# 2225_VumetreFrequencemetre.net
KiCad netlist of a schematic drawn in Altium Designer
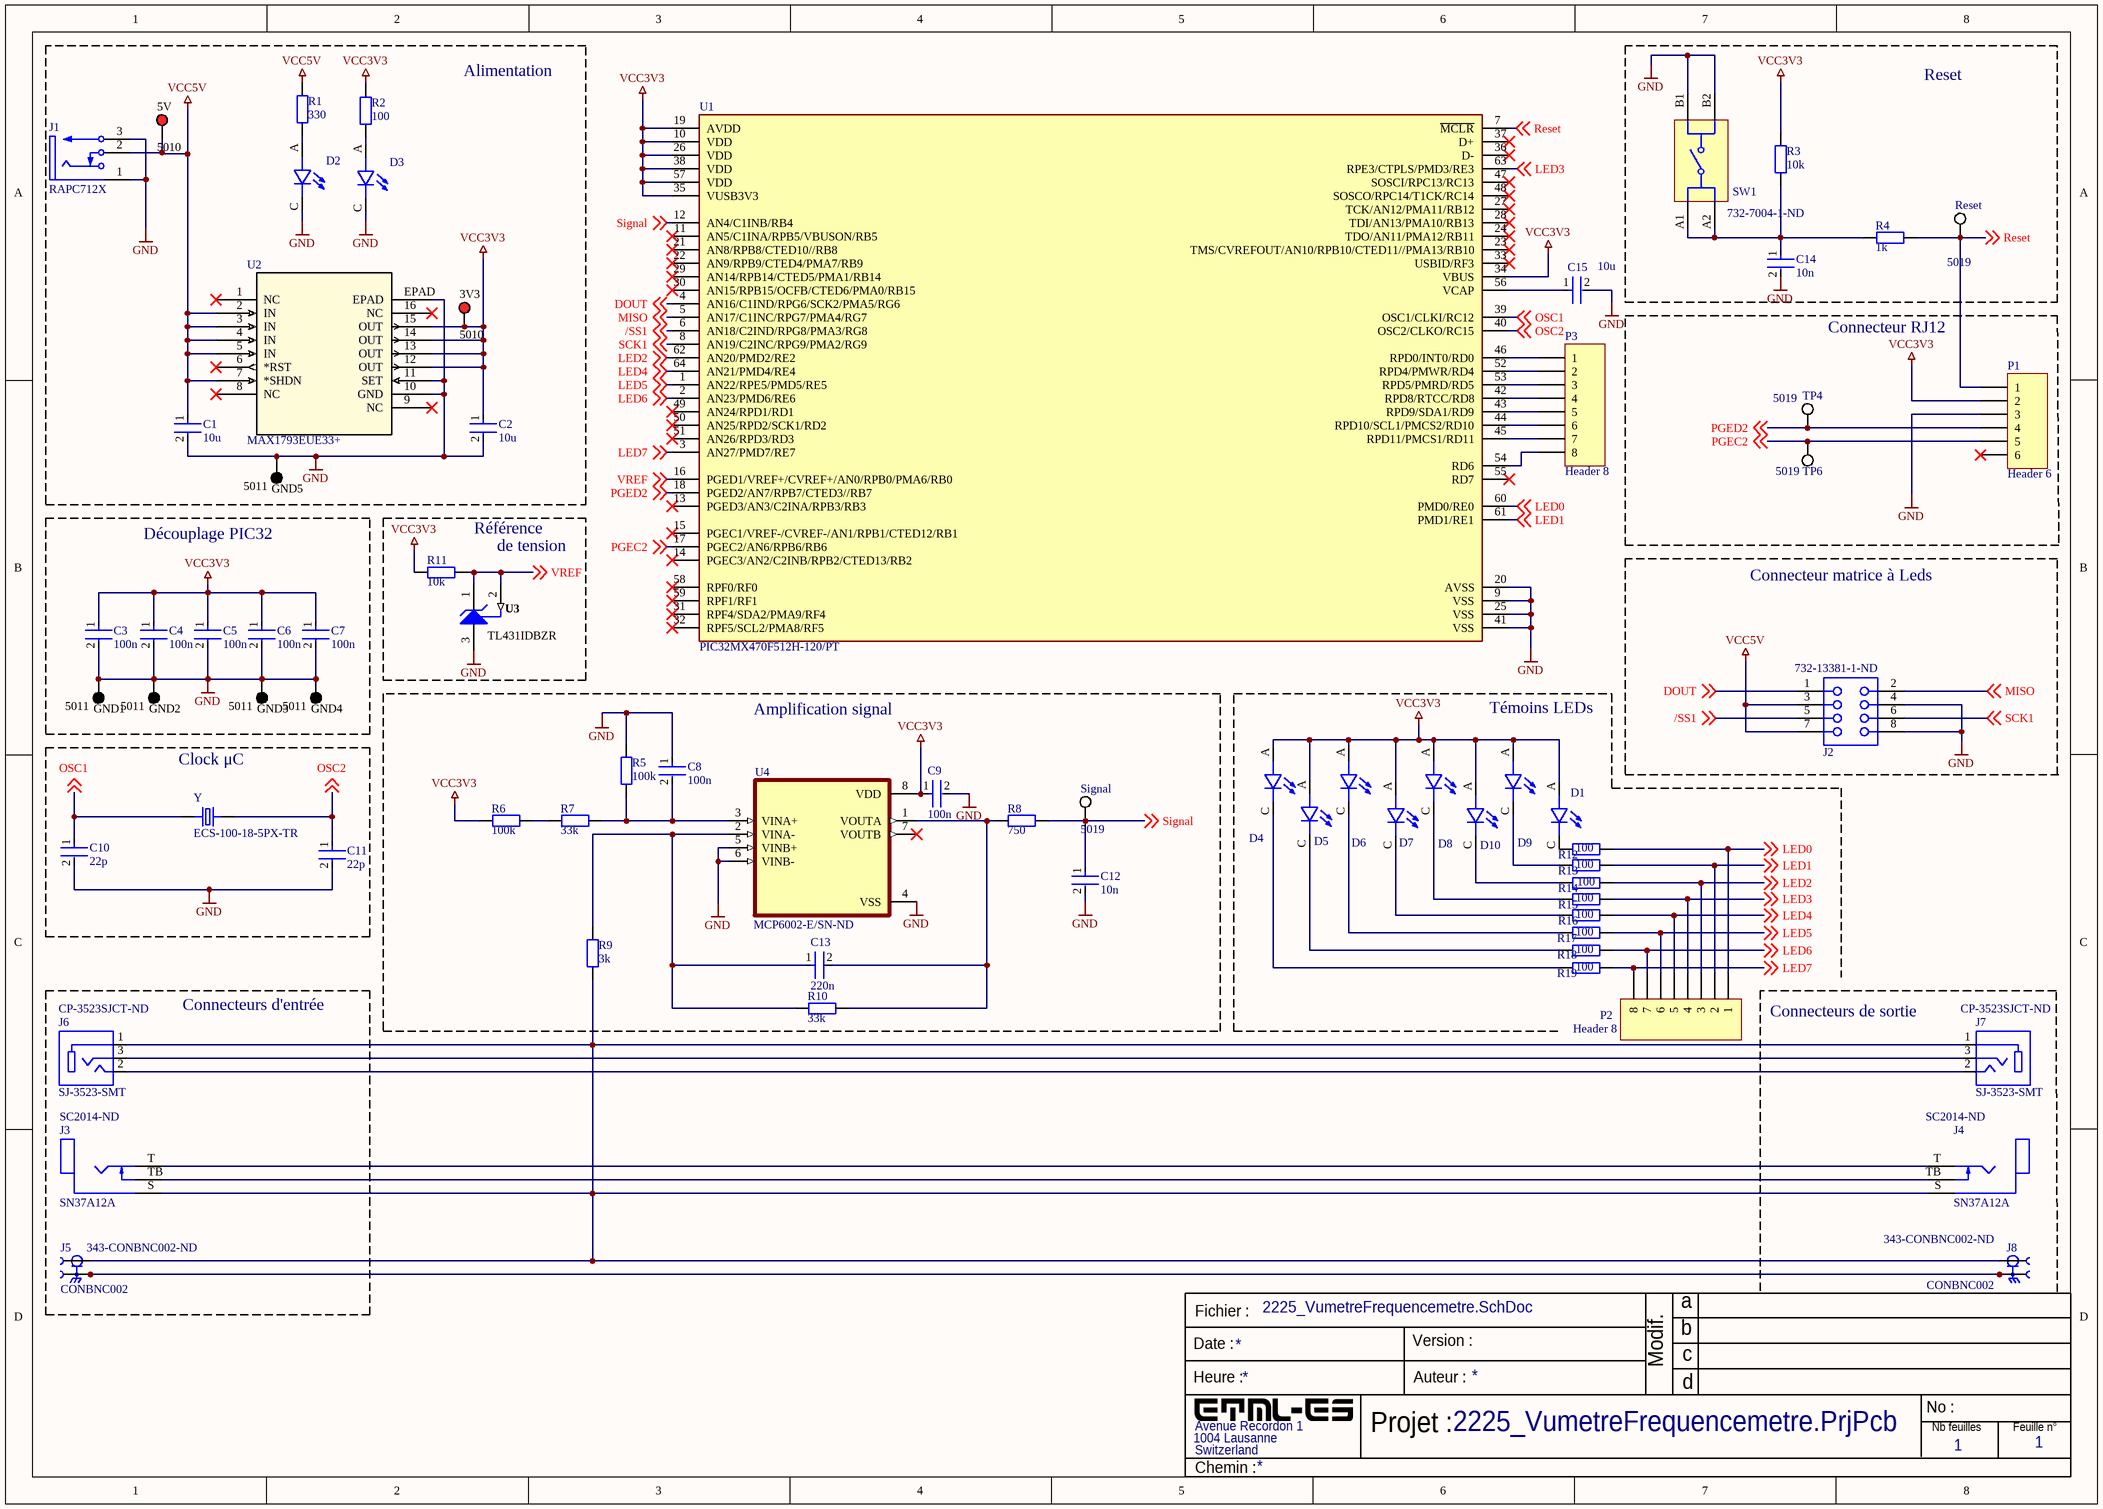
[diagram p0: 2225_VumetreFrequencemetre.SchDoc]

(export (version "E")
  (design (tool "Eeschema 10.0.6"))
  (components
    (comp (ref "3V3")
      (value "5010")
      (footprint "KSTN-5010_V")
      (description "Test Point, Red, Through Hole, RoHS, Bulk")
      (fields (field (name "MANUFACTURER") "Keystone"))
      (libsource (lib "Altium Content Vault") (part "TESTPOINT_RED"))
    )
    (comp (ref "5V")
      (value "5010")
      (footprint "KSTN-5010_V")
      (description "Test Point, Red, Through Hole, RoHS, Bulk")
      (fields (field (name "MANUFACTURER") "Keystone"))
      (libsource (lib "Altium Content Vault") (part "TESTPOINT_RED"))
    )
    (comp (ref "C1")
      (value "10u")
      (footprint "FP-GRM21B-0_15-IPC_C")
      (description "Chip Multilayer Ceramic Capacitors for General Purpose, 0805, 10uF, X5R, 15%, 10%, 25V")
      (fields (field (name "VOLTAGE") "25V") (field (name "TOLERANCE") "10%"))
      (libsource (lib "Altium Content Vault") (part "b4654b650e69147ec39a6b967a45e02"))
    )
    (comp (ref "C2")
      (value "10u")
      (footprint "FP-GRM21B-0_15-IPC_C")
      (description "Chip Multilayer Ceramic Capacitors for General Purpose, 0805, 10uF, X5R, 15%, 10%, 25V")
      (fields (field (name "VOLTAGE") "25V") (field (name "TOLERANCE") "10%"))
      (libsource (lib "Altium Content Vault") (part "b4654b650e69147ec39a6b967a45e02"))
    )
    (comp (ref "C3")
      (value "100n")
      (footprint "FP-GRM21B-0_15-IPC_C")
      (description "Chip Multilayer Ceramic Capacitors for General Purpose, 0805, 10uF, X5R, 15%, 10%, 25V")
      (fields (field (name "VOLTAGE") "25V") (field (name "TOLERANCE") "10%"))
      (libsource (lib "Altium Content Vault") (part "b4654b650e69147ec39a6b967a45e02"))
    )
    (comp (ref "C4")
      (value "100n")
      (footprint "FP-GRM21B-0_15-IPC_C")
      (description "Chip Multilayer Ceramic Capacitors for General Purpose, 0805, 10uF, X5R, 15%, 10%, 25V")
      (fields (field (name "VOLTAGE") "25V") (field (name "TOLERANCE") "10%"))
      (libsource (lib "Altium Content Vault") (part "b4654b650e69147ec39a6b967a45e02"))
    )
    (comp (ref "C5")
      (value "100n")
      (footprint "FP-GRM21B-0_15-IPC_C")
      (description "Chip Multilayer Ceramic Capacitors for General Purpose, 0805, 10uF, X5R, 15%, 10%, 25V")
      (fields (field (name "VOLTAGE") "25V") (field (name "TOLERANCE") "10%"))
      (libsource (lib "Altium Content Vault") (part "b4654b650e69147ec39a6b967a45e02"))
    )
    (comp (ref "C6")
      (value "100n")
      (footprint "FP-GRM21B-0_15-IPC_C")
      (description "Chip Multilayer Ceramic Capacitors for General Purpose, 0805, 10uF, X5R, 15%, 10%, 25V")
      (fields (field (name "VOLTAGE") "25V") (field (name "TOLERANCE") "10%"))
      (libsource (lib "Altium Content Vault") (part "b4654b650e69147ec39a6b967a45e02"))
    )
    (comp (ref "C7")
      (value "100n")
      (footprint "FP-GRM21B-0_15-IPC_C")
      (description "Chip Multilayer Ceramic Capacitors for General Purpose, 0805, 10uF, X5R, 15%, 10%, 25V")
      (fields (field (name "VOLTAGE") "25V") (field (name "TOLERANCE") "10%"))
      (libsource (lib "Altium Content Vault") (part "b4654b650e69147ec39a6b967a45e02"))
    )
    (comp (ref "C8")
      (value "100n")
      (footprint "FP-GRM21B-0_15-IPC_C")
      (description "Chip Multilayer Ceramic Capacitors for General Purpose, 0805, 10uF, X5R, 15%, 10%, 25V")
      (fields (field (name "VOLTAGE") "25V") (field (name "TOLERANCE") "10%"))
      (libsource (lib "Altium Content Vault") (part "b4654b650e69147ec39a6b967a45e02"))
    )
    (comp (ref "C9")
      (value "100n")
      (footprint "FP-GRM21B-0_15-IPC_C")
      (description "Chip Multilayer Ceramic Capacitors for General Purpose, 0805, 10uF, X5R, 15%, 10%, 25V")
      (fields (field (name "VOLTAGE") "25V") (field (name "TOLERANCE") "10%"))
      (libsource (lib "Altium Content Vault") (part "b4654b650e69147ec39a6b967a45e02"))
    )
    (comp (ref "C10")
      (value "22p")
      (footprint "FP-GRM21B-0_15-IPC_C")
      (description "Chip Multilayer Ceramic Capacitors for General Purpose, 0805, 10uF, X5R, 15%, 10%, 25V")
      (fields (field (name "VOLTAGE") "25V") (field (name "TOLERANCE") "10%"))
      (libsource (lib "Altium Content Vault") (part "b4654b650e69147ec39a6b967a45e02"))
    )
    (comp (ref "C11")
      (value "22p")
      (footprint "FP-GRM21B-0_15-IPC_C")
      (description "Chip Multilayer Ceramic Capacitors for General Purpose, 0805, 10uF, X5R, 15%, 10%, 25V")
      (fields (field (name "VOLTAGE") "25V") (field (name "TOLERANCE") "10%"))
      (libsource (lib "Altium Content Vault") (part "b4654b650e69147ec39a6b967a45e02"))
    )
    (comp (ref "C12")
      (value "10n")
      (footprint "FP-GRM21B-0_15-IPC_C")
      (description "Chip Multilayer Ceramic Capacitors for General Purpose, 0805, 10uF, X5R, 15%, 10%, 25V")
      (fields (field (name "VOLTAGE") "25V") (field (name "TOLERANCE") "10%"))
      (libsource (lib "Altium Content Vault") (part "b4654b650e69147ec39a6b967a45e02"))
    )
    (comp (ref "C13")
      (value "220n")
      (footprint "FP-GRM21B-0_15-IPC_C")
      (description "Chip Multilayer Ceramic Capacitors for General Purpose, 0805, 10uF, X5R, 15%, 10%, 25V")
      (fields (field (name "VOLTAGE") "25V") (field (name "TOLERANCE") "10%"))
      (libsource (lib "Altium Content Vault") (part "b4654b650e69147ec39a6b967a45e02"))
    )
    (comp (ref "C14")
      (value "10n")
      (footprint "FP-GRM21B-0_15-IPC_C")
      (description "Chip Multilayer Ceramic Capacitors for General Purpose, 0805, 10uF, X5R, 15%, 10%, 25V")
      (fields (field (name "VOLTAGE") "25V") (field (name "TOLERANCE") "10%"))
      (libsource (lib "Altium Content Vault") (part "b4654b650e69147ec39a6b967a45e02"))
    )
    (comp (ref "C15")
      (value "10u")
      (footprint "FP-GRM21B-0_15-IPC_C")
      (description "Chip Multilayer Ceramic Capacitors for General Purpose, 0805, 10uF, X5R, 15%, 10%, 25V")
      (fields (field (name "VOLTAGE") "25V") (field (name "TOLERANCE") "10%"))
      (libsource (lib "Altium Content Vault") (part "b4654b650e69147ec39a6b967a45e02"))
    )
    (comp (ref "D1")
      (value "LTST-C191KFKT")
      (footprint "LEDC1608X55N")
      (description "Orange 605nm LED Indication - Discrete 2V 0603 (1608 Metric)")
      (fields (field (name "MF") "Lite-On Inc."))
      (libsource (lib "LTST-C191KFKT") (part "LTST-C191KFKT"))
    )
    (comp (ref "D2")
      (value "LTST-C191KFKT")
      (footprint "LEDC1608X55N")
      (description "Orange 605nm LED Indication - Discrete 2V 0603 (1608 Metric)")
      (fields (field (name "MF") "Lite-On Inc."))
      (libsource (lib "LTST-C191KFKT") (part "LTST-C191KFKT"))
    )
    (comp (ref "D3")
      (value "LTST-C191KFKT")
      (footprint "LEDC1608X55N")
      (description "Orange 605nm LED Indication - Discrete 2V 0603 (1608 Metric)")
      (fields (field (name "MF") "Lite-On Inc."))
      (libsource (lib "LTST-C191KFKT") (part "LTST-C191KFKT"))
    )
    (comp (ref "D4")
      (value "LTST-C191KFKT")
      (footprint "LEDC1608X55N")
      (description "Orange 605nm LED Indication - Discrete 2V 0603 (1608 Metric)")
      (fields (field (name "MF") "Lite-On Inc."))
      (libsource (lib "LTST-C191KFKT") (part "LTST-C191KFKT"))
    )
    (comp (ref "D5")
      (value "LTST-C191KFKT")
      (footprint "LEDC1608X55N")
      (description "Orange 605nm LED Indication - Discrete 2V 0603 (1608 Metric)")
      (fields (field (name "MF") "Lite-On Inc."))
      (libsource (lib "LTST-C191KFKT") (part "LTST-C191KFKT"))
    )
    (comp (ref "D6")
      (value "LTST-C191KFKT")
      (footprint "LEDC1608X55N")
      (description "Orange 605nm LED Indication - Discrete 2V 0603 (1608 Metric)")
      (fields (field (name "MF") "Lite-On Inc."))
      (libsource (lib "LTST-C191KFKT") (part "LTST-C191KFKT"))
    )
    (comp (ref "D7")
      (value "LTST-C191KFKT")
      (footprint "LEDC1608X55N")
      (description "Orange 605nm LED Indication - Discrete 2V 0603 (1608 Metric)")
      (fields (field (name "MF") "Lite-On Inc."))
      (libsource (lib "LTST-C191KFKT") (part "LTST-C191KFKT"))
    )
    (comp (ref "D8")
      (value "LTST-C191KFKT")
      (footprint "LEDC1608X55N")
      (description "Orange 605nm LED Indication - Discrete 2V 0603 (1608 Metric)")
      (fields (field (name "MF") "Lite-On Inc."))
      (libsource (lib "LTST-C191KFKT") (part "LTST-C191KFKT"))
    )
    (comp (ref "D9")
      (value "LTST-C191KFKT")
      (footprint "LEDC1608X55N")
      (description "Orange 605nm LED Indication - Discrete 2V 0603 (1608 Metric)")
      (fields (field (name "MF") "Lite-On Inc."))
      (libsource (lib "LTST-C191KFKT") (part "LTST-C191KFKT"))
    )
    (comp (ref "D10")
      (value "LTST-C191KFKT")
      (footprint "LEDC1608X55N")
      (description "Orange 605nm LED Indication - Discrete 2V 0603 (1608 Metric)")
      (fields (field (name "MF") "Lite-On Inc."))
      (libsource (lib "LTST-C191KFKT") (part "LTST-C191KFKT"))
    )
    (comp (ref "GND1")
      (value "5011")
      (footprint "KSTN-5011_V")
      (description "Test Point, Black, Through Hole, RoHS, Bulk")
      (fields (field (name "MANUFACTURER") "Keystone"))
      (libsource (lib "Altium Content Vault") (part "TESTPOINT_BLACK"))
    )
    (comp (ref "GND2")
      (value "5011")
      (footprint "KSTN-5011_V")
      (description "Test Point, Black, Through Hole, RoHS, Bulk")
      (fields (field (name "MANUFACTURER") "Keystone"))
      (libsource (lib "Altium Content Vault") (part "TESTPOINT_BLACK"))
    )
    (comp (ref "GND3")
      (value "5011")
      (footprint "KSTN-5011_V")
      (description "Test Point, Black, Through Hole, RoHS, Bulk")
      (fields (field (name "MANUFACTURER") "Keystone"))
      (libsource (lib "Altium Content Vault") (part "TESTPOINT_BLACK"))
    )
    (comp (ref "GND4")
      (value "5011")
      (footprint "KSTN-5011_V")
      (description "Test Point, Black, Through Hole, RoHS, Bulk")
      (fields (field (name "MANUFACTURER") "Keystone"))
      (libsource (lib "Altium Content Vault") (part "TESTPOINT_BLACK"))
    )
    (comp (ref "GND5")
      (value "5011")
      (footprint "KSTN-5011_V")
      (description "Test Point, Black, Through Hole, RoHS, Bulk")
      (fields (field (name "MANUFACTURER") "Keystone"))
      (libsource (lib "Altium Content Vault") (part "TESTPOINT_BLACK"))
    )
    (comp (ref "J1")
      (value "RAPC712X")
      (footprint "SWITCH-RAPC712X-3_V")
      (description "Conn Powerjack Mini R/A PCMT, 5 A, 3-Pin THD, RoHS")
      (fields (field (name "MANUFACTURER") "Switchcraft"))
      (libsource (lib "Altium Content Vault") (part "SWITCH-RAPC712X-3"))
    )
    (comp (ref "J2")
      (value "61030821821")
      (footprint "61030821821")
      (description "WR-PHD Socket Header, SMT, Vertical, pitch 2.54mm, 2 Row, 8P")
      (fields
        (field (name "MANUFACTURER") "Wurth Elektronik")
        (field (name "SUPPLIER PART NUMBER 1") "732-13381-1-ND")
      )
      (libsource (lib "WR-PHD") (part "61030821821"))
    )
    (comp (ref "J3")
      (value "SN37A12A")
      (footprint "SWITCHCRAFT_SN37A12A")
      (description "Connecteur Jack 6.35mm")
      (fields (field (name "SUPPLIER PART NUMBER 1") "SC2014-ND"))
      (libsource (lib "SN37A12A") (part "SN37A12A"))
    )
    (comp (ref "J4")
      (value "SN37A12A")
      (footprint "SWITCHCRAFT_SN37A12A")
      (description "Connecteur Jack 6.35mm")
      (fields (field (name "SUPPLIER PART NUMBER 1") "SC2014-ND"))
      (libsource (lib "SN37A12A") (part "SN37A12A"))
    )
    (comp (ref "J5")
      (value "CONBNC002")
      (footprint "LINX_CONBNC002")
      (description "BNC Connector Jack, Female Socket 50Ohm Panel Mount, Through Hole, Right Angle Solder")
      (fields
        (field (name "MF") "Linx Technologies Inc.")
        (field (name "SUPPLIER PART NUMBER 1") "343-CONBNC002-ND")
      )
      (libsource (lib "CONBNC002") (part "CONBNC002"))
    )
    (comp (ref "J6")
      (value "SJ-3523-SMT")
      (footprint "CUI_SJ-3523-SMT")
      (description "3.50mm _0.141, 1/8, Mini Plug_ - Headphone Phone Jack Stereo _3 Conductor, TRS_ Connector Solder")
      (fields (field (name "MF") "CUI Devices") (field (name "SUPPLIER PART NUMBER 1") "CP-3523SJCT-ND"))
      (libsource (lib "SnapEDAsch") (part "SJ-3523-SMT"))
    )
    (comp (ref "J7")
      (value "SJ-3523-SMT")
      (footprint "CUI_SJ-3523-SMT")
      (description "3.50mm _0.141, 1/8, Mini Plug_ - Headphone Phone Jack Stereo _3 Conductor, TRS_ Connector Solder")
      (fields (field (name "MF") "CUI Devices") (field (name "SUPPLIER PART NUMBER 1") "CP-3523SJCT-ND"))
      (libsource (lib "SnapEDAsch") (part "SJ-3523-SMT"))
    )
    (comp (ref "J8")
      (value "CONBNC002")
      (footprint "LINX_CONBNC002")
      (description "BNC Connector Jack, Female Socket 50Ohm Panel Mount, Through Hole, Right Angle Solder")
      (fields
        (field (name "MF") "Linx Technologies Inc.")
        (field (name "SUPPLIER PART NUMBER 1") "343-CONBNC002-ND")
      )
      (libsource (lib "") (part "CONBNC002_1"))
    )
    (comp (ref "P1")
      (value "Header 6")
      (footprint "HDR1X6")
      (description "Header, 6-Pin")
      (fields (field (name "PUBLISHER") "Altium Limited"))
      (libsource (lib "Miscellaneous Connectors") (part "Header 6"))
    )
    (comp (ref "P2")
      (value "Header 8")
      (footprint "HDR1X8")
      (description "Header, 8-Pin")
      (fields (field (name "PUBLISHER") "Altium Limited"))
      (libsource (lib "Miscellaneous Connectors") (part "Header 8"))
    )
    (comp (ref "P3")
      (value "Header 8")
      (footprint "HDR1X8")
      (description "Header, 8-Pin")
      (fields (field (name "PUBLISHER") "Altium Limited"))
      (libsource (lib "") (part "Header 8_1"))
    )
    (comp (ref "R1")
      (value "330")
      (footprint "RESC2013X50X30ML20T20")
      (fields (field (name "MANUFACTURER") "Vishay Dale") (field (name "PART NUMBER") "CRCW08050000Z0EA"))
      (libsource (lib "") (part "RES_1"))
    )
    (comp (ref "R2")
      (value "100")
      (footprint "RESC2013X50X30ML20T20")
      (fields (field (name "MANUFACTURER") "Vishay Dale") (field (name "PART NUMBER") "CRCW08050000Z0EA"))
      (libsource (lib "") (part "RES_1"))
    )
    (comp (ref "R3")
      (value "10k")
      (footprint "RESC2013X50X30ML20T20")
      (fields (field (name "MANUFACTURER") "Vishay Dale") (field (name "PART NUMBER") "CRCW08050000Z0EA"))
      (libsource (lib "") (part "RES_1"))
    )
    (comp (ref "R4")
      (value "1k")
      (footprint "RESC2013X50X30ML20T20")
      (fields (field (name "MANUFACTURER") "Vishay Dale") (field (name "PART NUMBER") "CRCW08050000Z0EA"))
      (libsource (lib "Altium Content Vault") (part "RES"))
    )
    (comp (ref "R5")
      (value "100k")
      (footprint "RESC2013X50X30ML20T20")
      (fields (field (name "MANUFACTURER") "Vishay Dale") (field (name "PART NUMBER") "CRCW08050000Z0EA"))
      (libsource (lib "") (part "RES_2"))
    )
    (comp (ref "R6")
      (value "100k")
      (footprint "RESC2013X50X30ML20T20")
      (fields (field (name "MANUFACTURER") "Vishay Dale") (field (name "PART NUMBER") "CRCW08050000Z0EA"))
      (libsource (lib "Altium Content Vault") (part "RES"))
    )
    (comp (ref "R7")
      (value "33k")
      (footprint "RESC2013X50X30ML20T20")
      (fields (field (name "MANUFACTURER") "Vishay Dale") (field (name "PART NUMBER") "CRCW08050000Z0EA"))
      (libsource (lib "Altium Content Vault") (part "RES"))
    )
    (comp (ref "R8")
      (value "750")
      (footprint "RESC2013X50X30ML20T20")
      (fields (field (name "MANUFACTURER") "Vishay Dale") (field (name "PART NUMBER") "CRCW08050000Z0EA"))
      (libsource (lib "Altium Content Vault") (part "RES"))
    )
    (comp (ref "R9")
      (value "3k")
      (footprint "RESC2013X50X30ML20T20")
      (fields (field (name "MANUFACTURER") "Vishay Dale") (field (name "PART NUMBER") "CRCW08050000Z0EA"))
      (libsource (lib "") (part "RES_2"))
    )
    (comp (ref "R10")
      (value "33k")
      (footprint "RESC2013X50X30ML20T20")
      (fields (field (name "MANUFACTURER") "Vishay Dale") (field (name "PART NUMBER") "CRCW08050000Z0EA"))
      (libsource (lib "Altium Content Vault") (part "RES"))
    )
    (comp (ref "R11")
      (value "10k")
      (footprint "RESC2013X50X30ML20T20")
      (fields (field (name "MANUFACTURER") "Vishay Dale") (field (name "PART NUMBER") "CRCW08050000Z0EA"))
      (libsource (lib "Altium Content Vault") (part "RES"))
    )
    (comp (ref "R12")
      (value "100")
      (footprint "RESC2013X50X30ML20T20")
      (fields (field (name "MANUFACTURER") "Vishay Dale") (field (name "PART NUMBER") "CRCW08050000Z0EA"))
      (libsource (lib "Altium Content Vault") (part "RES"))
    )
    (comp (ref "R13")
      (value "100")
      (footprint "RESC2013X50X30ML20T20")
      (fields (field (name "MANUFACTURER") "Vishay Dale") (field (name "PART NUMBER") "CRCW08050000Z0EA"))
      (libsource (lib "Altium Content Vault") (part "RES"))
    )
    (comp (ref "R14")
      (value "100")
      (footprint "RESC2013X50X30ML20T20")
      (fields (field (name "MANUFACTURER") "Vishay Dale") (field (name "PART NUMBER") "CRCW08050000Z0EA"))
      (libsource (lib "Altium Content Vault") (part "RES"))
    )
    (comp (ref "R15")
      (value "100")
      (footprint "RESC2013X50X30ML20T20")
      (fields (field (name "MANUFACTURER") "Vishay Dale") (field (name "PART NUMBER") "CRCW08050000Z0EA"))
      (libsource (lib "Altium Content Vault") (part "RES"))
    )
    (comp (ref "R16")
      (value "100")
      (footprint "RESC2013X50X30ML20T20")
      (fields (field (name "MANUFACTURER") "Vishay Dale") (field (name "PART NUMBER") "CRCW08050000Z0EA"))
      (libsource (lib "Altium Content Vault") (part "RES"))
    )
    (comp (ref "R17")
      (value "100")
      (footprint "RESC2013X50X30ML20T20")
      (fields (field (name "MANUFACTURER") "Vishay Dale") (field (name "PART NUMBER") "CRCW08050000Z0EA"))
      (libsource (lib "Altium Content Vault") (part "RES"))
    )
    (comp (ref "R18")
      (value "100")
      (footprint "RESC2013X50X30ML20T20")
      (fields (field (name "MANUFACTURER") "Vishay Dale") (field (name "PART NUMBER") "CRCW08050000Z0EA"))
      (libsource (lib "Altium Content Vault") (part "RES"))
    )
    (comp (ref "R19")
      (value "100")
      (footprint "RESC2013X50X30ML20T20")
      (fields (field (name "MANUFACTURER") "Vishay Dale") (field (name "PART NUMBER") "CRCW08050000Z0EA"))
      (libsource (lib "Altium Content Vault") (part "RES"))
    )
    (comp (ref "Reset")
      (value "5019")
      (footprint "KSTN-5019_V")
      (description "Test Point, 1 Position SMD, RoHS, Tape and Reel")
      (libsource (lib "Altium Content Vault") (part "TESTPOINT_WHITE"))
    )
    (comp (ref "Signal")
      (value "5019")
      (footprint "KSTN-5019_V")
      (description "Test Point, 1 Position SMD, RoHS, Tape and Reel")
      (libsource (lib "Altium Content Vault") (part "TESTPOINT_WHITE"))
    )
    (comp (ref "SW1")
      (value "430182043816")
      (footprint "WS-TASV_L6W6H4.3_4301x20438x6")
      (description "WS-TASV SMT Tact Switch, L6 x W6 x H4.3mm, 160g, SPST-NO, 12V, 50mA")
      (fields
        (field (name "MANUFACTURER") "Wurth Elektronik")
        (field (name "SUPPLIER PART NUMBER 1") "732-7004-1-ND")
      )
      (libsource (lib "WS-TASV") (part "430182043816"))
    )
    (comp (ref "TP4")
      (value "5019")
      (footprint "KSTN-5019_V")
      (description "Test Point, 1 Position SMD, RoHS, Tape and Reel")
      (libsource (lib "Altium Content Vault") (part "TESTPOINT_WHITE"))
    )
    (comp (ref "TP6")
      (value "5019")
      (footprint "KSTN-5019_V")
      (description "Test Point, 1 Position SMD, RoHS, Tape and Reel")
      (libsource (lib "Altium Content Vault") (part "TESTPOINT_WHITE"))
    )
    (comp (ref "U1")
      (value "IC_Microchip_PIC32MX470F512H-120-PT_eec")
      (footprint "Microchip_C04-085B_0")
      (description "IC MCU 32BIT 512KB FLASH 64TQFP")
      (fields
        (field (name "PART NUMBER") "PIC32MX470F512H-120/PT")
        (field (name "MANUFACTURER") "Microchip")
        (field (name "MOUSER PART NUMBER") "579-MX470F512H120PT")
      )
      (libsource (lib "IC_Microchip_PIC32MX470F512H-120-PT_eec") (part "IC_Microchip_PIC32MX470F512H-120-PT_eec"))
    )
    (comp (ref "U2")
      (value "MAX1793EUE33+")
      (footprint "21-0108_U16E+3_MXM")
      (description "No Description Available")
      (fields (field (name "COPYRIGHT") "Copyright (C) 2023 Ultra Librarian. All rights reserved."))
      (libsource (lib "MAX1793EUE33&plus_") (part "MAX1793EUE33+"))
    )
    (comp (ref "U3")
      (value "TL431IDBZR")
      (footprint "DBZ0003A_L")
      (fields (field (name "MANUFACTURER") "Texas Instruments"))
      (libsource (lib "Altium Content Vault") (part "TI-TL431DBZ3"))
    )
    (comp (ref "U4")
      (value "MCP6002-E/SN")
      (footprint "SOIC127P599X175-8N")
      (description "General Purpose Amplifier 2 Circuit Rail-to-Rail 8-SOIC")
      (fields (field (name "MF") "Microchip") (field (name "SUPPLIER PART NUMBER 1") "MCP6002-E/SN-ND"))
      (libsource (lib "SnapEDAsch") (part "MCP6002-E/SN"))
    )
    (comp (ref "Y")
      (value "ECS-100-18-5PX-TR")
      (footprint "XTAL_ECS-100-18-5PX-TR")
      (description "10MHz Â±30ppm Crystal 18pF 50 Ohms HC-49/US")
      (fields (field (name "MF") "ECS Inc.") (field (name "DIGI-KEY_PART_NUMBER") "XC1288CT-ND"))
      (libsource (lib "SnapEDAsch") (part "ECS-100-18-5PX-TR"))
    )
  )
  (nets
    (net (code "1") (name "DOUT") (class "Default")
      (node (ref "J2") (pin "1") (pinfunction "1_1") (pintype "passive"))
      (node (ref "U1") (pin "4") (pinfunction "AN16/C1IND/RPG6/SCK2/PMA5/RG6_4") (pintype "passive"))
    )
    (net (code "2") (name "GND") (class "Default")
      (node (ref "C1") (pin "2") (pinfunction "2_2") (pintype "passive"))
      (node (ref "C10") (pin "2") (pinfunction "2_2") (pintype "passive"))
      (node (ref "C11") (pin "2") (pinfunction "2_2") (pintype "passive"))
      (node (ref "C12") (pin "2") (pinfunction "2_2") (pintype "passive"))
      (node (ref "C14") (pin "2") (pinfunction "2_2") (pintype "passive"))
      (node (ref "C15") (pin "2") (pinfunction "2_2") (pintype "passive"))
      (node (ref "C2") (pin "2") (pinfunction "2_2") (pintype "passive"))
      (node (ref "C3") (pin "2") (pinfunction "2_2") (pintype "passive"))
      (node (ref "C4") (pin "2") (pinfunction "2_2") (pintype "passive"))
      (node (ref "C5") (pin "2") (pinfunction "2_2") (pintype "passive"))
      (node (ref "C6") (pin "2") (pinfunction "2_2") (pintype "passive"))
      (node (ref "C7") (pin "2") (pinfunction "2_2") (pintype "passive"))
      (node (ref "C8") (pin "1") (pinfunction "1_1") (pintype "passive"))
      (node (ref "C9") (pin "2") (pinfunction "2_2") (pintype "passive"))
      (node (ref "D2") (pin "C") (pinfunction "C_C") (pintype "passive"))
      (node (ref "D3") (pin "C") (pinfunction "C_C") (pintype "passive"))
      (node (ref "GND1") (pin "1") (pinfunction "1_1") (pintype "passive"))
      (node (ref "GND2") (pin "1") (pinfunction "1_1") (pintype "passive"))
      (node (ref "GND3") (pin "1") (pinfunction "1_1") (pintype "passive"))
      (node (ref "GND4") (pin "1") (pinfunction "1_1") (pintype "passive"))
      (node (ref "GND5") (pin "1") (pinfunction "1_1") (pintype "passive"))
      (node (ref "J1") (pin "1") (pinfunction "1_1") (pintype "passive"))
      (node (ref "J1") (pin "3") (pinfunction "3_3") (pintype "passive"))
      (node (ref "J2") (pin "4") (pinfunction "4_4") (pintype "passive"))
      (node (ref "J2") (pin "8") (pinfunction "8_8") (pintype "passive"))
      (node (ref "P1") (pin "3") (pinfunction "3_3") (pintype "passive"))
      (node (ref "R5") (pin "2") (pinfunction "2_2") (pintype "passive"))
      (node (ref "SW1") (pin "B1") (pinfunction "B1_B1") (pintype "passive"))
      (node (ref "SW1") (pin "B2") (pinfunction "B2_B2") (pintype "passive"))
      (node (ref "U1") (pin "20") (pinfunction "AVSS_20") (pintype "passive"))
      (node (ref "U1") (pin "25") (pinfunction "VSS_25") (pintype "passive"))
      (node (ref "U1") (pin "41") (pinfunction "VSS_41") (pintype "passive"))
      (node (ref "U1") (pin "9") (pinfunction "VSS_9") (pintype "passive"))
      (node (ref "U2") (pin "10") (pinfunction "GND_10") (pintype "power_in"))
      (node (ref "U2") (pin "11") (pinfunction "SET_11") (pintype "input"))
      (node (ref "U2") (pin "EPAD") (pinfunction "EPAD_EPAD") (pintype "passive"))
      (node (ref "U3") (pin "3") (pinfunction "ANODE_3") (pintype "passive"))
      (node (ref "U4") (pin "4") (pinfunction "VSS_4") (pintype "power_in"))
      (node (ref "U4") (pin "5") (pinfunction "VINB+_5") (pintype "input"))
      (node (ref "U4") (pin "6") (pinfunction "VINB-_6") (pintype "input"))
    )
    (net (code "3") (name "LED0") (class "Default")
      (node (ref "P2") (pin "1") (pinfunction "1_1") (pintype "passive"))
      (node (ref "R12") (pin "2") (pinfunction "2_2") (pintype "passive"))
      (node (ref "U1") (pin "60") (pinfunction "PMD0/RE0_60") (pintype "passive"))
    )
    (net (code "4") (name "LED1") (class "Default")
      (node (ref "P2") (pin "2") (pinfunction "2_2") (pintype "passive"))
      (node (ref "R13") (pin "2") (pinfunction "2_2") (pintype "passive"))
      (node (ref "U1") (pin "61") (pinfunction "PMD1/RE1_61") (pintype "passive"))
    )
    (net (code "5") (name "LED2") (class "Default")
      (node (ref "P2") (pin "3") (pinfunction "3_3") (pintype "passive"))
      (node (ref "R14") (pin "2") (pinfunction "2_2") (pintype "passive"))
      (node (ref "U1") (pin "62") (pinfunction "AN20/PMD2/RE2_62") (pintype "passive"))
    )
    (net (code "6") (name "LED3") (class "Default")
      (node (ref "P2") (pin "4") (pinfunction "4_4") (pintype "passive"))
      (node (ref "R15") (pin "2") (pinfunction "2_2") (pintype "passive"))
      (node (ref "U1") (pin "63") (pinfunction "RPE3/CTPLS/PMD3/RE3_63") (pintype "passive"))
    )
    (net (code "7") (name "LED4") (class "Default")
      (node (ref "P2") (pin "5") (pinfunction "5_5") (pintype "passive"))
      (node (ref "R16") (pin "2") (pinfunction "2_2") (pintype "passive"))
      (node (ref "U1") (pin "64") (pinfunction "AN21/PMD4/RE4_64") (pintype "passive"))
    )
    (net (code "8") (name "LED5") (class "Default")
      (node (ref "P2") (pin "6") (pinfunction "6_6") (pintype "passive"))
      (node (ref "R17") (pin "2") (pinfunction "2_2") (pintype "passive"))
      (node (ref "U1") (pin "1") (pinfunction "AN22/RPE5/PMD5/RE5_1") (pintype "passive"))
    )
    (net (code "9") (name "LED6") (class "Default")
      (node (ref "P2") (pin "7") (pinfunction "7_7") (pintype "passive"))
      (node (ref "R18") (pin "2") (pinfunction "2_2") (pintype "passive"))
      (node (ref "U1") (pin "2") (pinfunction "AN23/PMD6/RE6_2") (pintype "passive"))
    )
    (net (code "10") (name "LED7") (class "Default")
      (node (ref "P2") (pin "8") (pinfunction "8_8") (pintype "passive"))
      (node (ref "R19") (pin "2") (pinfunction "2_2") (pintype "passive"))
      (node (ref "U1") (pin "3") (pinfunction "AN27/PMD7/RE7_3") (pintype "passive"))
    )
    (net (code "11") (name "MISO") (class "Default")
      (node (ref "J2") (pin "2") (pinfunction "2_2") (pintype "passive"))
      (node (ref "U1") (pin "5") (pinfunction "AN17/C1INC/RPG7/PMA4/RG7_5") (pintype "passive"))
    )
    (net (code "12") (name "Net-(C14-Pad1)") (class "Default")
      (node (ref "C14") (pin "1") (pinfunction "1_1") (pintype "passive"))
      (node (ref "R3") (pin "2") (pinfunction "2_2") (pintype "passive"))
      (node (ref "R4") (pin "1") (pinfunction "1_1") (pintype "passive"))
      (node (ref "SW1") (pin "A1") (pinfunction "A1_A1") (pintype "passive"))
      (node (ref "SW1") (pin "A2") (pinfunction "A2_A2") (pintype "passive"))
    )
    (net (code "13") (name "Net-(D1-PadC)") (class "Default")
      (node (ref "D1") (pin "C") (pinfunction "C_C") (pintype "passive"))
      (node (ref "R12") (pin "1") (pinfunction "1_1") (pintype "passive"))
    )
    (net (code "14") (name "Net-(D2-PadA)") (class "Default")
      (node (ref "D2") (pin "A") (pinfunction "A_A") (pintype "passive"))
      (node (ref "R1") (pin "2") (pinfunction "2_2") (pintype "passive"))
    )
    (net (code "15") (name "Net-(D3-PadA)") (class "Default")
      (node (ref "D3") (pin "A") (pinfunction "A_A") (pintype "passive"))
      (node (ref "R2") (pin "2") (pinfunction "2_2") (pintype "passive"))
    )
    (net (code "16") (name "Net-(D4-PadC)") (class "Default")
      (node (ref "D4") (pin "C") (pinfunction "C_C") (pintype "passive"))
      (node (ref "R19") (pin "1") (pinfunction "1_1") (pintype "passive"))
    )
    (net (code "17") (name "Net-(D5-PadC)") (class "Default")
      (node (ref "D5") (pin "C") (pinfunction "C_C") (pintype "passive"))
      (node (ref "R18") (pin "1") (pinfunction "1_1") (pintype "passive"))
    )
    (net (code "18") (name "Net-(D6-PadC)") (class "Default")
      (node (ref "D6") (pin "C") (pinfunction "C_C") (pintype "passive"))
      (node (ref "R17") (pin "1") (pinfunction "1_1") (pintype "passive"))
    )
    (net (code "19") (name "Net-(D7-PadC)") (class "Default")
      (node (ref "D7") (pin "C") (pinfunction "C_C") (pintype "passive"))
      (node (ref "R16") (pin "1") (pinfunction "1_1") (pintype "passive"))
    )
    (net (code "20") (name "Net-(D8-PadC)") (class "Default")
      (node (ref "D8") (pin "C") (pinfunction "C_C") (pintype "passive"))
      (node (ref "R15") (pin "1") (pinfunction "1_1") (pintype "passive"))
    )
    (net (code "21") (name "Net-(D9-PadC)") (class "Default")
      (node (ref "D9") (pin "C") (pinfunction "C_C") (pintype "passive"))
      (node (ref "R13") (pin "1") (pinfunction "1_1") (pintype "passive"))
    )
    (net (code "22") (name "Net-(D10-PadC)") (class "Default")
      (node (ref "D10") (pin "C") (pinfunction "C_C") (pintype "passive"))
      (node (ref "R14") (pin "1") (pinfunction "1_1") (pintype "passive"))
    )
    (net (code "23") (name "Net-(J3-PadS)") (class "Default")
      (node (ref "J3") (pin "S") (pinfunction "S_S") (pintype "passive"))
      (node (ref "J4") (pin "S") (pinfunction "S_S") (pintype "passive"))
      (node (ref "J5") (pin "1") (pinfunction "1_1") (pintype "passive"))
      (node (ref "J6") (pin "1") (pinfunction "1_1") (pintype "passive"))
      (node (ref "J7") (pin "1") (pinfunction "1_1") (pintype "passive"))
      (node (ref "J8") (pin "1") (pinfunction "1_1") (pintype "passive"))
      (node (ref "R9") (pin "1") (pinfunction "1_1") (pintype "passive"))
    )
    (net (code "24") (name "Net-(J3-PadT)") (class "Default")
      (node (ref "J3") (pin "T") (pinfunction "T_T") (pintype "passive"))
      (node (ref "J4") (pin "T") (pinfunction "T_T") (pintype "passive"))
    )
    (net (code "25") (name "Net-(J3-PadTB)") (class "Default")
      (node (ref "J3") (pin "TB") (pinfunction "TB_TB") (pintype "passive"))
      (node (ref "J4") (pin "TB") (pinfunction "TB_TB") (pintype "passive"))
    )
    (net (code "26") (name "Net-(J5-2-PadS1)") (class "Default")
      (node (ref "J5") (pin "2") (pinfunction "2_2") (pintype "passive"))
      (node (ref "J5") (pin "S1") (pinfunction "2_S1") (pintype "passive"))
      (node (ref "J5") (pin "S2") (pinfunction "2_S2") (pintype "passive"))
      (node (ref "J8") (pin "2") (pinfunction "2_2") (pintype "passive"))
      (node (ref "J8") (pin "S1") (pinfunction "2_S1") (pintype "passive"))
      (node (ref "J8") (pin "S2") (pinfunction "2_S2") (pintype "passive"))
    )
    (net (code "27") (name "Net-(J6-Pad2)") (class "Default")
      (node (ref "J6") (pin "2") (pinfunction "2_2") (pintype "passive"))
      (node (ref "J7") (pin "2") (pinfunction "2_2") (pintype "passive"))
    )
    (net (code "28") (name "Net-(J6-Pad3)") (class "Default")
      (node (ref "J6") (pin "3") (pinfunction "3_3") (pintype "passive"))
      (node (ref "J7") (pin "3") (pinfunction "3_3") (pintype "passive"))
    )
    (net (code "29") (name "Net-(R6-Pad2)") (class "Default")
      (node (ref "R6") (pin "2") (pinfunction "2_2") (pintype "passive"))
      (node (ref "R7") (pin "1") (pinfunction "1_1") (pintype "passive"))
    )
    (net (code "30") (name "Net-(U1-RD6)") (class "Default")
      (node (ref "P3") (pin "8") (pinfunction "8_8") (pintype "passive"))
      (node (ref "U1") (pin "54") (pinfunction "RD6_54") (pintype "passive"))
    )
    (net (code "31") (name "Net-(U1-RPD0{slash}INT0{slash}RD0)") (class "Default")
      (node (ref "P3") (pin "1") (pinfunction "1_1") (pintype "passive"))
      (node (ref "U1") (pin "46") (pinfunction "RPD0/INT0/RD0_46") (pintype "passive"))
    )
    (net (code "32") (name "Net-(U1-RPD4{slash}PMWR{slash}RD4)") (class "Default")
      (node (ref "P3") (pin "2") (pinfunction "2_2") (pintype "passive"))
      (node (ref "U1") (pin "52") (pinfunction "RPD4/PMWR/RD4_52") (pintype "passive"))
    )
    (net (code "33") (name "Net-(U1-RPD5{slash}PMRD{slash}RD5)") (class "Default")
      (node (ref "P3") (pin "3") (pinfunction "3_3") (pintype "passive"))
      (node (ref "U1") (pin "53") (pinfunction "RPD5/PMRD/RD5_53") (pintype "passive"))
    )
    (net (code "34") (name "Net-(U1-RPD8{slash}RTCC{slash}RD8)") (class "Default")
      (node (ref "P3") (pin "4") (pinfunction "4_4") (pintype "passive"))
      (node (ref "U1") (pin "42") (pinfunction "RPD8/RTCC/RD8_42") (pintype "passive"))
    )
    (net (code "35") (name "Net-(U1-RPD9{slash}SDA1{slash}RD9)") (class "Default")
      (node (ref "P3") (pin "5") (pinfunction "5_5") (pintype "passive"))
      (node (ref "U1") (pin "43") (pinfunction "RPD9/SDA1/RD9_43") (pintype "passive"))
    )
    (net (code "36") (name "Net-(U1-RPD10{slash}SCL1{slash}PMCS2{slash}RD10)") (class "Default")
      (node (ref "P3") (pin "6") (pinfunction "6_6") (pintype "passive"))
      (node (ref "U1") (pin "44") (pinfunction "RPD10/SCL1/PMCS2/RD10_44") (pintype "passive"))
    )
    (net (code "37") (name "Net-(U1-RPD11{slash}PMCS1{slash}RD11)") (class "Default")
      (node (ref "P3") (pin "7") (pinfunction "7_7") (pintype "passive"))
      (node (ref "U1") (pin "45") (pinfunction "RPD11/PMCS1/RD11_45") (pintype "passive"))
    )
    (net (code "38") (name "Net-(U1-VCAP)") (class "Default")
      (node (ref "C15") (pin "1") (pinfunction "1_1") (pintype "passive"))
      (node (ref "U1") (pin "56") (pinfunction "VCAP_56") (pintype "passive"))
    )
    (net (code "39") (name "Net-(U4-VINA+)") (class "Default")
      (node (ref "C8") (pin "2") (pinfunction "2_2") (pintype "passive"))
      (node (ref "R5") (pin "1") (pinfunction "1_1") (pintype "passive"))
      (node (ref "R7") (pin "2") (pinfunction "2_2") (pintype "passive"))
      (node (ref "U4") (pin "3") (pinfunction "VINA+_3") (pintype "input"))
    )
    (net (code "40") (name "Net-(U4-VINA-)") (class "Default")
      (node (ref "C13") (pin "1") (pinfunction "1_1") (pintype "passive"))
      (node (ref "R10") (pin "1") (pinfunction "1_1") (pintype "passive"))
      (node (ref "R9") (pin "2") (pinfunction "2_2") (pintype "passive"))
      (node (ref "U4") (pin "2") (pinfunction "VINA-_2") (pintype "input"))
    )
    (net (code "41") (name "Net-(U4-VOUTA)") (class "Default")
      (node (ref "C13") (pin "2") (pinfunction "2_2") (pintype "passive"))
      (node (ref "R10") (pin "2") (pinfunction "2_2") (pintype "passive"))
      (node (ref "R8") (pin "1") (pinfunction "1_1") (pintype "passive"))
      (node (ref "U4") (pin "1") (pinfunction "VOUTA_1") (pintype "output"))
    )
    (net (code "42") (name "OSC1") (class "Default")
      (node (ref "C10") (pin "1") (pinfunction "1_1") (pintype "passive"))
      (node (ref "U1") (pin "39") (pinfunction "OSC1/CLKI/RC12_39") (pintype "passive"))
      (node (ref "Y") (pin "1") (pinfunction "1_1") (pintype "passive"))
    )
    (net (code "43") (name "OSC2") (class "Default")
      (node (ref "C11") (pin "1") (pinfunction "1_1") (pintype "passive"))
      (node (ref "U1") (pin "40") (pinfunction "OSC2/CLKO/RC15_40") (pintype "passive"))
      (node (ref "Y") (pin "2") (pinfunction "2_2") (pintype "passive"))
    )
    (net (code "44") (name "PGEC2") (class "Default")
      (node (ref "P1") (pin "5") (pinfunction "5_5") (pintype "passive"))
      (node (ref "TP6") (pin "1") (pinfunction "1_1") (pintype "passive"))
      (node (ref "U1") (pin "17") (pinfunction "PGEC2/AN6/RPB6/RB6_17") (pintype "passive"))
    )
    (net (code "45") (name "PGED2") (class "Default")
      (node (ref "P1") (pin "4") (pinfunction "4_4") (pintype "passive"))
      (node (ref "TP4") (pin "1") (pinfunction "1_1") (pintype "passive"))
      (node (ref "U1") (pin "18") (pinfunction "PGED2/AN7/RPB7/CTED3//RB7_18") (pintype "passive"))
    )
    (net (code "46") (name "Reset") (class "Default")
      (node (ref "P1") (pin "1") (pinfunction "1_1") (pintype "passive"))
      (node (ref "R4") (pin "2") (pinfunction "2_2") (pintype "passive"))
      (node (ref "Reset") (pin "1") (pinfunction "1_1") (pintype "passive"))
      (node (ref "U1") (pin "7") (pinfunction "~{MCLR}_7") (pintype "passive"))
    )
    (net (code "47") (name "SCK1") (class "Default")
      (node (ref "J2") (pin "6") (pinfunction "6_6") (pintype "passive"))
      (node (ref "U1") (pin "8") (pinfunction "AN19/C2INC/RPG9/PMA2/RG9_8") (pintype "passive"))
    )
    (net (code "48") (name "Signal") (class "Default")
      (node (ref "C12") (pin "1") (pinfunction "1_1") (pintype "passive"))
      (node (ref "R8") (pin "2") (pinfunction "2_2") (pintype "passive"))
      (node (ref "Signal") (pin "1") (pinfunction "1_1") (pintype "passive"))
      (node (ref "U1") (pin "12") (pinfunction "AN4/C1INB/RB4_12") (pintype "passive"))
    )
    (net (code "49") (name "VCC3V3") (class "Default")
      (node (ref "3V3") (pin "1") (pinfunction "1_1") (pintype "passive"))
      (node (ref "C2") (pin "1") (pinfunction "1_1") (pintype "passive"))
      (node (ref "C3") (pin "1") (pinfunction "1_1") (pintype "passive"))
      (node (ref "C4") (pin "1") (pinfunction "1_1") (pintype "passive"))
      (node (ref "C5") (pin "1") (pinfunction "1_1") (pintype "passive"))
      (node (ref "C6") (pin "1") (pinfunction "1_1") (pintype "passive"))
      (node (ref "C7") (pin "1") (pinfunction "1_1") (pintype "passive"))
      (node (ref "C9") (pin "1") (pinfunction "1_1") (pintype "passive"))
      (node (ref "D1") (pin "A") (pinfunction "A_A") (pintype "passive"))
      (node (ref "D10") (pin "A") (pinfunction "A_A") (pintype "passive"))
      (node (ref "D4") (pin "A") (pinfunction "A_A") (pintype "passive"))
      (node (ref "D5") (pin "A") (pinfunction "A_A") (pintype "passive"))
      (node (ref "D6") (pin "A") (pinfunction "A_A") (pintype "passive"))
      (node (ref "D7") (pin "A") (pinfunction "A_A") (pintype "passive"))
      (node (ref "D8") (pin "A") (pinfunction "A_A") (pintype "passive"))
      (node (ref "D9") (pin "A") (pinfunction "A_A") (pintype "passive"))
      (node (ref "P1") (pin "2") (pinfunction "2_2") (pintype "passive"))
      (node (ref "R11") (pin "1") (pinfunction "1_1") (pintype "passive"))
      (node (ref "R2") (pin "1") (pinfunction "1_1") (pintype "passive"))
      (node (ref "R3") (pin "1") (pinfunction "1_1") (pintype "passive"))
      (node (ref "R6") (pin "1") (pinfunction "1_1") (pintype "passive"))
      (node (ref "U1") (pin "10") (pinfunction "VDD_10") (pintype "passive"))
      (node (ref "U1") (pin "19") (pinfunction "AVDD_19") (pintype "passive"))
      (node (ref "U1") (pin "26") (pinfunction "VDD_26") (pintype "passive"))
      (node (ref "U1") (pin "34") (pinfunction "VBUS_34") (pintype "passive"))
      (node (ref "U1") (pin "35") (pinfunction "VUSB3V3_35") (pintype "passive"))
      (node (ref "U1") (pin "38") (pinfunction "VDD_38") (pintype "passive"))
      (node (ref "U1") (pin "57") (pinfunction "VDD_57") (pintype "passive"))
      (node (ref "U2") (pin "12") (pinfunction "OUT_12") (pintype "power_in"))
      (node (ref "U2") (pin "13") (pinfunction "OUT_13") (pintype "power_in"))
      (node (ref "U2") (pin "14") (pinfunction "OUT_14") (pintype "power_in"))
      (node (ref "U2") (pin "15") (pinfunction "OUT_15") (pintype "power_in"))
      (node (ref "U4") (pin "8") (pinfunction "VDD_8") (pintype "power_in"))
    )
    (net (code "50") (name "VCC5V") (class "Default")
      (node (ref "5V") (pin "1") (pinfunction "1_1") (pintype "passive"))
      (node (ref "C1") (pin "1") (pinfunction "1_1") (pintype "passive"))
      (node (ref "J1") (pin "2") (pinfunction "2_2") (pintype "passive"))
      (node (ref "J2") (pin "3") (pinfunction "3_3") (pintype "passive"))
      (node (ref "J2") (pin "7") (pinfunction "7_7") (pintype "passive"))
      (node (ref "R1") (pin "1") (pinfunction "1_1") (pintype "passive"))
      (node (ref "U2") (pin "2") (pinfunction "IN_2") (pintype "input"))
      (node (ref "U2") (pin "3") (pinfunction "IN_3") (pintype "input"))
      (node (ref "U2") (pin "4") (pinfunction "IN_4") (pintype "input"))
      (node (ref "U2") (pin "5") (pinfunction "IN_5") (pintype "input"))
      (node (ref "U2") (pin "7") (pinfunction "*SHDN_7") (pintype "input"))
    )
    (net (code "51") (name "VREF") (class "Default")
      (node (ref "R11") (pin "2") (pinfunction "2_2") (pintype "passive"))
      (node (ref "U1") (pin "16") (pinfunction "PGED1/VREF+/CVREF+/AN0/RPB0/PMA6/RB0_16") (pintype "passive"))
      (node (ref "U3") (pin "1") (pinfunction "CATHODE_1") (pintype "passive"))
      (node (ref "U3") (pin "2") (pinfunction "REF_2") (pintype "input"))
    )
    (net (code "52") (name "unconnected-(P1-Pad6)") (class "Default")
      (node (ref "P1") (pin "6") (pinfunction "6_6") (pintype "passive+no_connect"))
    )
    (net (code "53") (name "unconnected-(U1-AN5{slash}C1INA{slash}RPB5{slash}VBUSON{slash}RB5-Pad11)") (class "Default")
      (node (ref "U1") (pin "11") (pinfunction "AN5/C1INA/RPB5/VBUSON/RB5_11") (pintype "passive+no_connect"))
    )
    (net (code "54") (name "unconnected-(U1-AN8{slash}RPB8{slash}CTED10{slash}{slash}RB8-Pad21)") (class "Default")
      (node (ref "U1") (pin "21") (pinfunction "AN8/RPB8/CTED10//RB8_21") (pintype "passive+no_connect"))
    )
    (net (code "55") (name "unconnected-(U1-AN9{slash}RPB9{slash}CTED4{slash}PMA7{slash}RB9-Pad22)") (class "Default")
      (node (ref "U1") (pin "22") (pinfunction "AN9/RPB9/CTED4/PMA7/RB9_22") (pintype "passive+no_connect"))
    )
    (net (code "56") (name "unconnected-(U1-AN14{slash}RPB14{slash}CTED5{slash}PMA1{slash}RB14-Pad29)") (class "Default")
      (node (ref "U1") (pin "29") (pinfunction "AN14/RPB14/CTED5/PMA1/RB14_29") (pintype "passive+no_connect"))
    )
    (net (code "57") (name "unconnected-(U1-AN15{slash}RPB15{slash}OCFB{slash}CTED6{slash}PMA0{slash}RB15-Pad30)") (class "Default")
      (node (ref "U1") (pin "30") (pinfunction "AN15/RPB15/OCFB/CTED6/PMA0/RB15_30") (pintype "passive+no_connect"))
    )
    (net (code "58") (name "unconnected-(U1-AN24{slash}RPD1{slash}RD1-Pad49)") (class "Default")
      (node (ref "U1") (pin "49") (pinfunction "AN24/RPD1/RD1_49") (pintype "passive+no_connect"))
    )
    (net (code "59") (name "unconnected-(U1-AN25{slash}RPD2{slash}SCK1{slash}RD2-Pad50)") (class "Default")
      (node (ref "U1") (pin "50") (pinfunction "AN25/RPD2/SCK1/RD2_50") (pintype "passive+no_connect"))
    )
    (net (code "60") (name "unconnected-(U1-AN26{slash}RPD3{slash}RD3-Pad51)") (class "Default")
      (node (ref "U1") (pin "51") (pinfunction "AN26/RPD3/RD3_51") (pintype "passive+no_connect"))
    )
    (net (code "61") (name "unconnected-(U1-D+-Pad37)") (class "Default")
      (node (ref "U1") (pin "37") (pinfunction "D+_37") (pintype "passive+no_connect"))
    )
    (net (code "62") (name "unconnected-(U1-D--Pad36)") (class "Default")
      (node (ref "U1") (pin "36") (pinfunction "D-_36") (pintype "passive+no_connect"))
    )
    (net (code "63") (name "unconnected-(U1-PGEC1{slash}VREF-{slash}CVREF-{slash}AN1{slash}RPB1{slash}CTED12{slash}RB1-Pad15)") (class "Default")
      (node (ref "U1") (pin "15") (pinfunction "PGEC1/VREF-/CVREF-/AN1/RPB1/CTED12/RB1_15") (pintype "passive+no_connect"))
    )
    (net (code "64") (name "unconnected-(U1-PGEC3{slash}AN2{slash}C2INB{slash}RPB2{slash}CTED13{slash}RB2-Pad14)") (class "Default")
      (node (ref "U1") (pin "14") (pinfunction "PGEC3/AN2/C2INB/RPB2/CTED13/RB2_14") (pintype "passive+no_connect"))
    )
    (net (code "65") (name "unconnected-(U1-PGED3{slash}AN3{slash}C2INA{slash}RPB3{slash}RB3-Pad13)") (class "Default")
      (node (ref "U1") (pin "13") (pinfunction "PGED3/AN3/C2INA/RPB3/RB3_13") (pintype "passive+no_connect"))
    )
    (net (code "66") (name "unconnected-(U1-RD7-Pad55)") (class "Default")
      (node (ref "U1") (pin "55") (pinfunction "RD7_55") (pintype "passive+no_connect"))
    )
    (net (code "67") (name "unconnected-(U1-RPF0{slash}RF0-Pad58)") (class "Default")
      (node (ref "U1") (pin "58") (pinfunction "RPF0/RF0_58") (pintype "passive+no_connect"))
    )
    (net (code "68") (name "unconnected-(U1-RPF1{slash}RF1-Pad59)") (class "Default")
      (node (ref "U1") (pin "59") (pinfunction "RPF1/RF1_59") (pintype "passive+no_connect"))
    )
    (net (code "69") (name "unconnected-(U1-RPF4{slash}SDA2{slash}PMA9{slash}RF4-Pad31)") (class "Default")
      (node (ref "U1") (pin "31") (pinfunction "RPF4/SDA2/PMA9/RF4_31") (pintype "passive+no_connect"))
    )
    (net (code "70") (name "unconnected-(U1-RPF5{slash}SCL2{slash}PMA8{slash}RF5-Pad32)") (class "Default")
      (node (ref "U1") (pin "32") (pinfunction "RPF5/SCL2/PMA8/RF5_32") (pintype "passive+no_connect"))
    )
    (net (code "71") (name "unconnected-(U1-SOSCI{slash}RPC13{slash}RC13-Pad47)") (class "Default")
      (node (ref "U1") (pin "47") (pinfunction "SOSCI/RPC13/RC13_47") (pintype "passive+no_connect"))
    )
    (net (code "72") (name "unconnected-(U1-SOSCO{slash}RPC14{slash}T1CK{slash}RC14-Pad48)") (class "Default")
      (node (ref "U1") (pin "48") (pinfunction "SOSCO/RPC14/T1CK/RC14_48") (pintype "passive+no_connect"))
    )
    (net (code "73") (name "unconnected-(U1-TCK{slash}AN12{slash}PMA11{slash}RB12-Pad27)") (class "Default")
      (node (ref "U1") (pin "27") (pinfunction "TCK/AN12/PMA11/RB12_27") (pintype "passive+no_connect"))
    )
    (net (code "74") (name "unconnected-(U1-TDI{slash}AN13{slash}PMA10{slash}RB13-Pad28)") (class "Default")
      (node (ref "U1") (pin "28") (pinfunction "TDI/AN13/PMA10/RB13_28") (pintype "passive+no_connect"))
    )
    (net (code "75") (name "unconnected-(U1-TDO{slash}AN11{slash}PMA12{slash}RB11-Pad24)") (class "Default")
      (node (ref "U1") (pin "24") (pinfunction "TDO/AN11/PMA12/RB11_24") (pintype "passive+no_connect"))
    )
    (net (code "76") (name "unconnected-(U1-TMS{slash}CVREFOUT{slash}AN10{slash}RPB10{slash}CTED11{slash}{slash}PMA13{slash}RB10-Pad23)") (class "Default")
      (node (ref "U1") (pin "23") (pinfunction "TMS/CVREFOUT/AN10/RPB10/CTED11//PMA13/RB10_23") (pintype "passive+no_connect"))
    )
    (net (code "77") (name "unconnected-(U1-USBID{slash}RF3-Pad33)") (class "Default")
      (node (ref "U1") (pin "33") (pinfunction "USBID/RF3_33") (pintype "passive+no_connect"))
    )
    (net (code "78") (name "unconnected-(U2-*RST-Pad6)") (class "Default")
      (node (ref "U2") (pin "6") (pinfunction "*RST_6") (pintype "output+no_connect"))
    )
    (net (code "79") (name "unconnected-(U2-NC-Pad1)") (class "Default")
      (node (ref "U2") (pin "1") (pinfunction "NC_1") (pintype "passive+no_connect"))
    )
    (net (code "80") (name "unconnected-(U2-NC-Pad8)") (class "Default")
      (node (ref "U2") (pin "8") (pinfunction "NC_8") (pintype "passive+no_connect"))
    )
    (net (code "81") (name "unconnected-(U2-NC-Pad9)") (class "Default")
      (node (ref "U2") (pin "9") (pinfunction "NC_9") (pintype "passive+no_connect"))
    )
    (net (code "82") (name "unconnected-(U2-NC-Pad16)") (class "Default")
      (node (ref "U2") (pin "16") (pinfunction "NC_16") (pintype "passive+no_connect"))
    )
    (net (code "83") (name "unconnected-(U4-VOUTB-Pad7)") (class "Default")
      (node (ref "U4") (pin "7") (pinfunction "VOUTB_7") (pintype "output+no_connect"))
    )
    (net (code "84") (name "{slash}SS1") (class "Default")
      (node (ref "J2") (pin "5") (pinfunction "5_5") (pintype "passive"))
      (node (ref "U1") (pin "6") (pinfunction "AN18/C2IND/RPG8/PMA3/RG8_6") (pintype "passive"))
    )
  )
)
